# RS_iface.net
KiCad netlist of a schematic drawn in Altium Designer
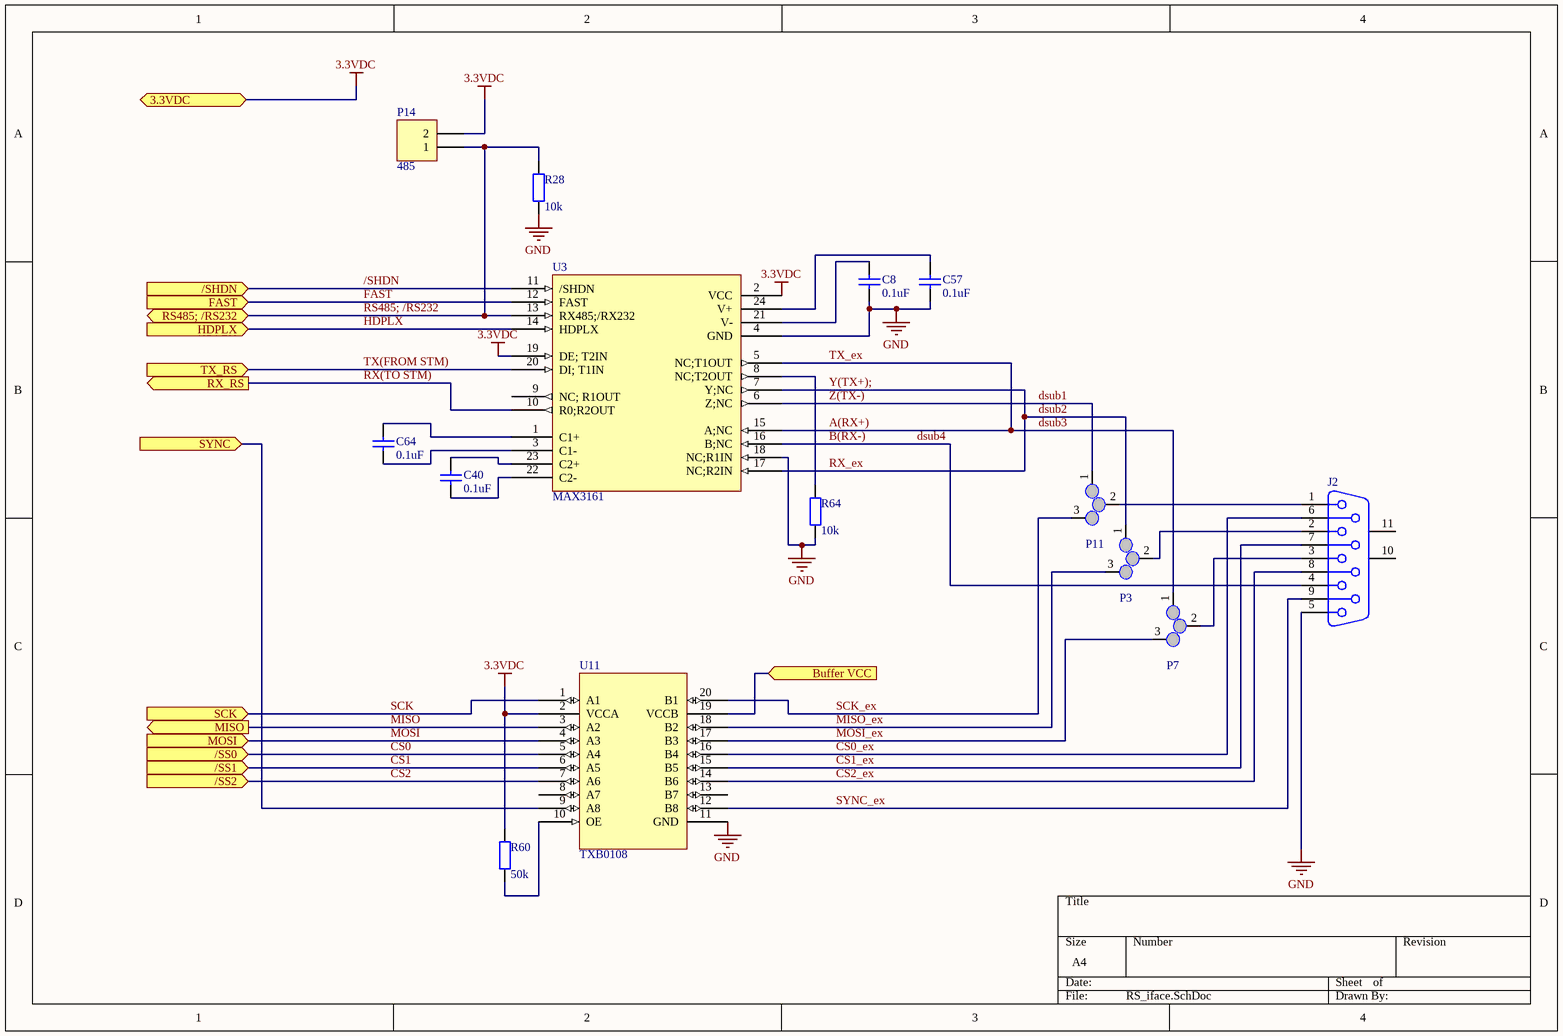
[diagram p0: RS_iface.SchDoc]

(export (version "E")
  (design (tool "Eeschema 10.0.6"))
  (components
    (comp (ref "C8")
      (value "0.1uF")
      (footprint "C_0603")
      (description "Capacitor")
      (fields (field (name "Comment") "Cap") (field (name "PUBLISHER") "Altium Limited"))
      (libsource (lib "AX_Altium_v2.3") (part "C0603"))
    )
    (comp (ref "C40")
      (value "0.1uF")
      (footprint "C_0603")
      (description "Capacitor")
      (fields (field (name "Comment") "Cap") (field (name "PUBLISHER") "Altium Limited"))
      (libsource (lib "AX_Altium_v2.3") (part "C0603"))
    )
    (comp (ref "C57")
      (value "0.1uF")
      (footprint "C_0603")
      (description "Capacitor")
      (fields (field (name "Comment") "Cap") (field (name "PUBLISHER") "Altium Limited"))
      (libsource (lib "AX_Altium_v2.3") (part "C0603"))
    )
    (comp (ref "C64")
      (value "0.1uF")
      (footprint "C_0603")
      (description "Capacitor")
      (fields (field (name "Comment") "Cap") (field (name "PUBLISHER") "Altium Limited"))
      (libsource (lib "AX_Altium_v2.3") (part "C0603"))
    )
    (comp (ref "J2")
      (value "DSUB Male")
      (footprint "PcbLib1:DSUB1.385-2H9M")
      (description "DSUB9 Male connector")
      (fields (field (name "PUBLISHER") "Altium Limited"))
      (libsource (lib "Miscellaneous Connectors") (part "D Connector 9"))
    )
    (comp (ref "P3")
      (value "SWI_CONN")
      (footprint "SW_SPDT")
      (description "Soldering switch")
      (libsource (lib "Add_lib") (part "SWI_CONN"))
    )
    (comp (ref "P7")
      (value "SWI_CONN")
      (footprint "SW_SPDT")
      (description "Soldering switch")
      (libsource (lib "Add_lib") (part "SWI_CONN"))
    )
    (comp (ref "P11")
      (value "SWI_CONN")
      (footprint "SW_SPDT")
      (description "Soldering switch")
      (libsource (lib "Add_lib") (part "SWI_CONN"))
    )
    (comp (ref "P14")
      (value "485")
      (footprint "HDR1X2")
      (description "Header, 2-Pin, 2.54mm pitch")
      (fields (field (name "PUBLISHER") "Altium Limited"))
      (libsource (lib "Miscellaneous Connectors") (part "Header 2H"))
    )
    (comp (ref "R28")
      (value "10k")
      (footprint "R_0603")
      (description "Resistor")
      (fields (field (name "Comment") "Res") (field (name "PUBLISHER") "Altium Limited"))
      (libsource (lib "AX_Altium_v2.3") (part "Res2"))
    )
    (comp (ref "R60")
      (value "50k")
      (footprint "R_0603")
      (description "Resistor")
      (fields (field (name "Comment") "Res") (field (name "PUBLISHER") "Altium Limited"))
      (libsource (lib "AX_Altium_v2.3") (part "Res2"))
    )
    (comp (ref "R64")
      (value "10k")
      (footprint "R_0603")
      (description "Resistor")
      (fields (field (name "Comment") "Res") (field (name "PUBLISHER") "Altium Limited"))
      (libsource (lib "AX_Altium_v2.3") (part "Res2"))
    )
    (comp (ref "U3")
      (value "MAX3161")
      (footprint "DB024")
      (description "Multitrancivier")
      (libsource (lib "Add_lib") (part "MAX3161"))
    )
    (comp (ref "U11")
      (value "TXB0108")
      (footprint "TSOP65P640X120-20N")
      (description "SPI buffer")
      (libsource (lib "Add_lib") (part "TXB0108"))
    )
  )
  (nets
    (net (code "1") (name "/A(RX+)") (class "Default")
      (node (ref "P7") (pin "1") (pintype "passive"))
      (node (ref "U3") (pin "15") (pinfunction "A;NC_15") (pintype "input"))
      (node (ref "U3") (pin "5") (pinfunction "NC;T1OUT_5") (pintype "output"))
    )
    (net (code "2") (name "/B(RX-)") (class "Default")
      (node (ref "J2") (pin "4") (pinfunction "4_4") (pintype "passive"))
      (node (ref "U3") (pin "16") (pinfunction "B;NC_16") (pintype "input"))
    )
    (net (code "3") (name "/Buffer VCC") (class "Default")
      (node (ref "U11") (pin "19") (pinfunction "VCCB_19") (pintype "passive"))
    )
    (net (code "4") (name "/CS0") (class "Default")
      (node (ref "U11") (pin "5") (pinfunction "A4_5") (pintype "bidirectional"))
    )
    (net (code "5") (name "/CS0_ex") (class "Default")
      (node (ref "J2") (pin "6") (pinfunction "6_6") (pintype "passive"))
      (node (ref "U11") (pin "16") (pinfunction "B4_16") (pintype "bidirectional"))
    )
    (net (code "6") (name "/CS1") (class "Default")
      (node (ref "U11") (pin "6") (pinfunction "A5_6") (pintype "bidirectional"))
    )
    (net (code "7") (name "/CS1_ex") (class "Default")
      (node (ref "J2") (pin "7") (pinfunction "7_7") (pintype "passive"))
      (node (ref "U11") (pin "15") (pinfunction "B5_15") (pintype "bidirectional"))
    )
    (net (code "8") (name "/CS2") (class "Default")
      (node (ref "U11") (pin "7") (pinfunction "A6_7") (pintype "bidirectional"))
    )
    (net (code "9") (name "/CS2_ex") (class "Default")
      (node (ref "J2") (pin "8") (pinfunction "8_8") (pintype "passive"))
      (node (ref "U11") (pin "14") (pinfunction "B6_14") (pintype "bidirectional"))
    )
    (net (code "10") (name "/FAST") (class "Default")
      (node (ref "U3") (pin "12") (pinfunction "FAST_12") (pintype "input"))
    )
    (net (code "11") (name "/HDPLX") (class "Default")
      (node (ref "U3") (pin "14") (pinfunction "HDPLX_14") (pintype "input"))
    )
    (net (code "12") (name "/MISO") (class "Default")
      (node (ref "U11") (pin "3") (pinfunction "A2_3") (pintype "bidirectional"))
    )
    (net (code "13") (name "/MISO_ex") (class "Default")
      (node (ref "P3") (pin "3") (pintype "passive"))
      (node (ref "U11") (pin "18") (pinfunction "B2_18") (pintype "bidirectional"))
    )
    (net (code "14") (name "/MOSI") (class "Default")
      (node (ref "U11") (pin "4") (pinfunction "A3_4") (pintype "bidirectional"))
    )
    (net (code "15") (name "/MOSI_ex") (class "Default")
      (node (ref "P7") (pin "3") (pintype "passive"))
      (node (ref "U11") (pin "17") (pinfunction "B3_17") (pintype "bidirectional"))
    )
    (net (code "16") (name "/RS485; {slash}RS232") (class "Default")
      (node (ref "P14") (pin "1") (pinfunction "1_1") (pintype "passive"))
      (node (ref "R28") (pin "2") (pinfunction "2_2") (pintype "passive"))
      (node (ref "U3") (pin "13") (pinfunction "RX485;/RX232_13") (pintype "input"))
    )
    (net (code "17") (name "/RX(TO STM)") (class "Default")
      (node (ref "U3") (pin "10") (pinfunction "R0;R2OUT_10") (pintype "output"))
    )
    (net (code "18") (name "/RX_ex") (class "Default")
      (node (ref "P3") (pin "1") (pintype "passive"))
      (node (ref "U3") (pin "17") (pinfunction "NC;R2IN_17") (pintype "input"))
      (node (ref "U3") (pin "7") (pinfunction "Y;NC_7") (pintype "output"))
    )
    (net (code "19") (name "/SCK") (class "Default")
      (node (ref "U11") (pin "1") (pinfunction "A1_1") (pintype "bidirectional"))
    )
    (net (code "20") (name "/SCK_ex") (class "Default")
      (node (ref "P11") (pin "3") (pintype "passive"))
      (node (ref "U11") (pin "20") (pinfunction "B1_20") (pintype "bidirectional"))
    )
    (net (code "21") (name "/SYNC") (class "Default")
      (node (ref "U11") (pin "9") (pinfunction "A8_9") (pintype "bidirectional"))
    )
    (net (code "22") (name "/SYNC_ex") (class "Default")
      (node (ref "J2") (pin "9") (pinfunction "9_9") (pintype "passive"))
      (node (ref "U11") (pin "12") (pinfunction "B8_12") (pintype "bidirectional"))
    )
    (net (code "23") (name "/TX(FROM STM)") (class "Default")
      (node (ref "U3") (pin "20") (pinfunction "DI;_T1IN_20") (pintype "input"))
    )
    (net (code "24") (name "/Z(TX-)") (class "Default")
      (node (ref "P11") (pin "1") (pintype "passive"))
      (node (ref "U3") (pin "6") (pinfunction "Z;NC_6") (pintype "output"))
    )
    (net (code "25") (name "/{slash}SHDN") (class "Default")
      (node (ref "U3") (pin "11") (pinfunction "/SHDN_11") (pintype "input"))
    )
    (net (code "26") (name "3.3VDC") (class "Default")
      (node (ref "P14") (pin "2") (pinfunction "2_2") (pintype "passive"))
      (node (ref "R60") (pin "2") (pinfunction "2_2") (pintype "passive"))
      (node (ref "U11") (pin "2") (pinfunction "VCCA_2") (pintype "passive"))
      (node (ref "U3") (pin "19") (pinfunction "DE;_T2IN_19") (pintype "input"))
      (node (ref "U3") (pin "2") (pinfunction "VCC_2") (pintype "passive"))
    )
    (net (code "27") (name "GND") (class "Default")
      (node (ref "C57") (pin "2") (pinfunction "2_2") (pintype "passive"))
      (node (ref "C8") (pin "2") (pinfunction "2_2") (pintype "passive"))
      (node (ref "J2") (pin "5") (pinfunction "5_5") (pintype "passive"))
      (node (ref "R28") (pin "1") (pinfunction "1_1") (pintype "passive"))
      (node (ref "R64") (pin "1") (pinfunction "1_1") (pintype "passive"))
      (node (ref "U11") (pin "11") (pinfunction "GND_11") (pintype "passive"))
      (node (ref "U3") (pin "18") (pinfunction "NC;R1IN_18") (pintype "input"))
      (node (ref "U3") (pin "4") (pinfunction "GND_4") (pintype "passive"))
    )
    (net (code "28") (name "Net-(J2-Pad1)") (class "Default")
      (node (ref "J2") (pin "1") (pinfunction "1_1") (pintype "passive"))
      (node (ref "P11") (pin "2") (pintype "passive"))
    )
    (net (code "29") (name "Net-(J2-Pad2)") (class "Default")
      (node (ref "J2") (pin "2") (pinfunction "2_2") (pintype "passive"))
      (node (ref "P3") (pin "2") (pintype "passive"))
    )
    (net (code "30") (name "Net-(J2-Pad3)") (class "Default")
      (node (ref "J2") (pin "3") (pinfunction "3_3") (pintype "passive"))
      (node (ref "P7") (pin "2") (pintype "passive"))
    )
    (net (code "31") (name "Net-(U3-C1+)") (class "Default")
      (node (ref "C64") (pin "1") (pinfunction "1_1") (pintype "passive"))
      (node (ref "U3") (pin "1") (pinfunction "C1+_1") (pintype "passive"))
    )
    (net (code "32") (name "Net-(U3-C1-)") (class "Default")
      (node (ref "C64") (pin "2") (pinfunction "2_2") (pintype "passive"))
      (node (ref "U3") (pin "3") (pinfunction "C1-_3") (pintype "passive"))
    )
    (net (code "33") (name "Net-(U3-C2+)") (class "Default")
      (node (ref "C40") (pin "1") (pinfunction "1_1") (pintype "passive"))
      (node (ref "U3") (pin "23") (pinfunction "C2+_23") (pintype "passive"))
    )
    (net (code "34") (name "Net-(U3-C2-)") (class "Default")
      (node (ref "C40") (pin "2") (pinfunction "2_2") (pintype "passive"))
      (node (ref "U3") (pin "22") (pinfunction "C2-_22") (pintype "passive"))
    )
    (net (code "35") (name "Net-(U3-NC;T2OUT)") (class "Default")
      (node (ref "R64") (pin "2") (pinfunction "2_2") (pintype "passive"))
      (node (ref "U3") (pin "8") (pinfunction "NC;T2OUT_8") (pintype "output"))
    )
    (net (code "36") (name "Net-(U3-V+)") (class "Default")
      (node (ref "C57") (pin "1") (pinfunction "1_1") (pintype "passive"))
      (node (ref "U3") (pin "24") (pinfunction "V+_24") (pintype "passive"))
    )
    (net (code "37") (name "Net-(U3-V-)") (class "Default")
      (node (ref "C8") (pin "1") (pinfunction "1_1") (pintype "passive"))
      (node (ref "U3") (pin "21") (pinfunction "V-_21") (pintype "passive"))
    )
    (net (code "38") (name "Net-(U11-OE)") (class "Default")
      (node (ref "R60") (pin "1") (pinfunction "1_1") (pintype "passive"))
      (node (ref "U11") (pin "10") (pinfunction "OE_10") (pintype "input"))
    )
    (net (code "39") (name "unconnected-(J2-MH1-Pad10)") (class "Default")
      (node (ref "J2") (pin "10") (pinfunction "MH1_10") (pintype "passive"))
    )
    (net (code "40") (name "unconnected-(J2-MH2-Pad11)") (class "Default")
      (node (ref "J2") (pin "11") (pinfunction "MH2_11") (pintype "passive"))
    )
    (net (code "41") (name "unconnected-(U3-NC;_R1OUT-Pad9)") (class "Default")
      (node (ref "U3") (pin "9") (pinfunction "NC;_R1OUT_9") (pintype "output"))
    )
    (net (code "42") (name "unconnected-(U11-A7-Pad8)") (class "Default")
      (node (ref "U11") (pin "8") (pinfunction "A7_8") (pintype "bidirectional"))
    )
    (net (code "43") (name "unconnected-(U11-B7-Pad13)") (class "Default")
      (node (ref "U11") (pin "13") (pinfunction "B7_13") (pintype "bidirectional"))
    )
  )
)
